# EdgePowerMeter_EasyEDA.net
KiCad netlist of a schematic drawn in EasyEDA
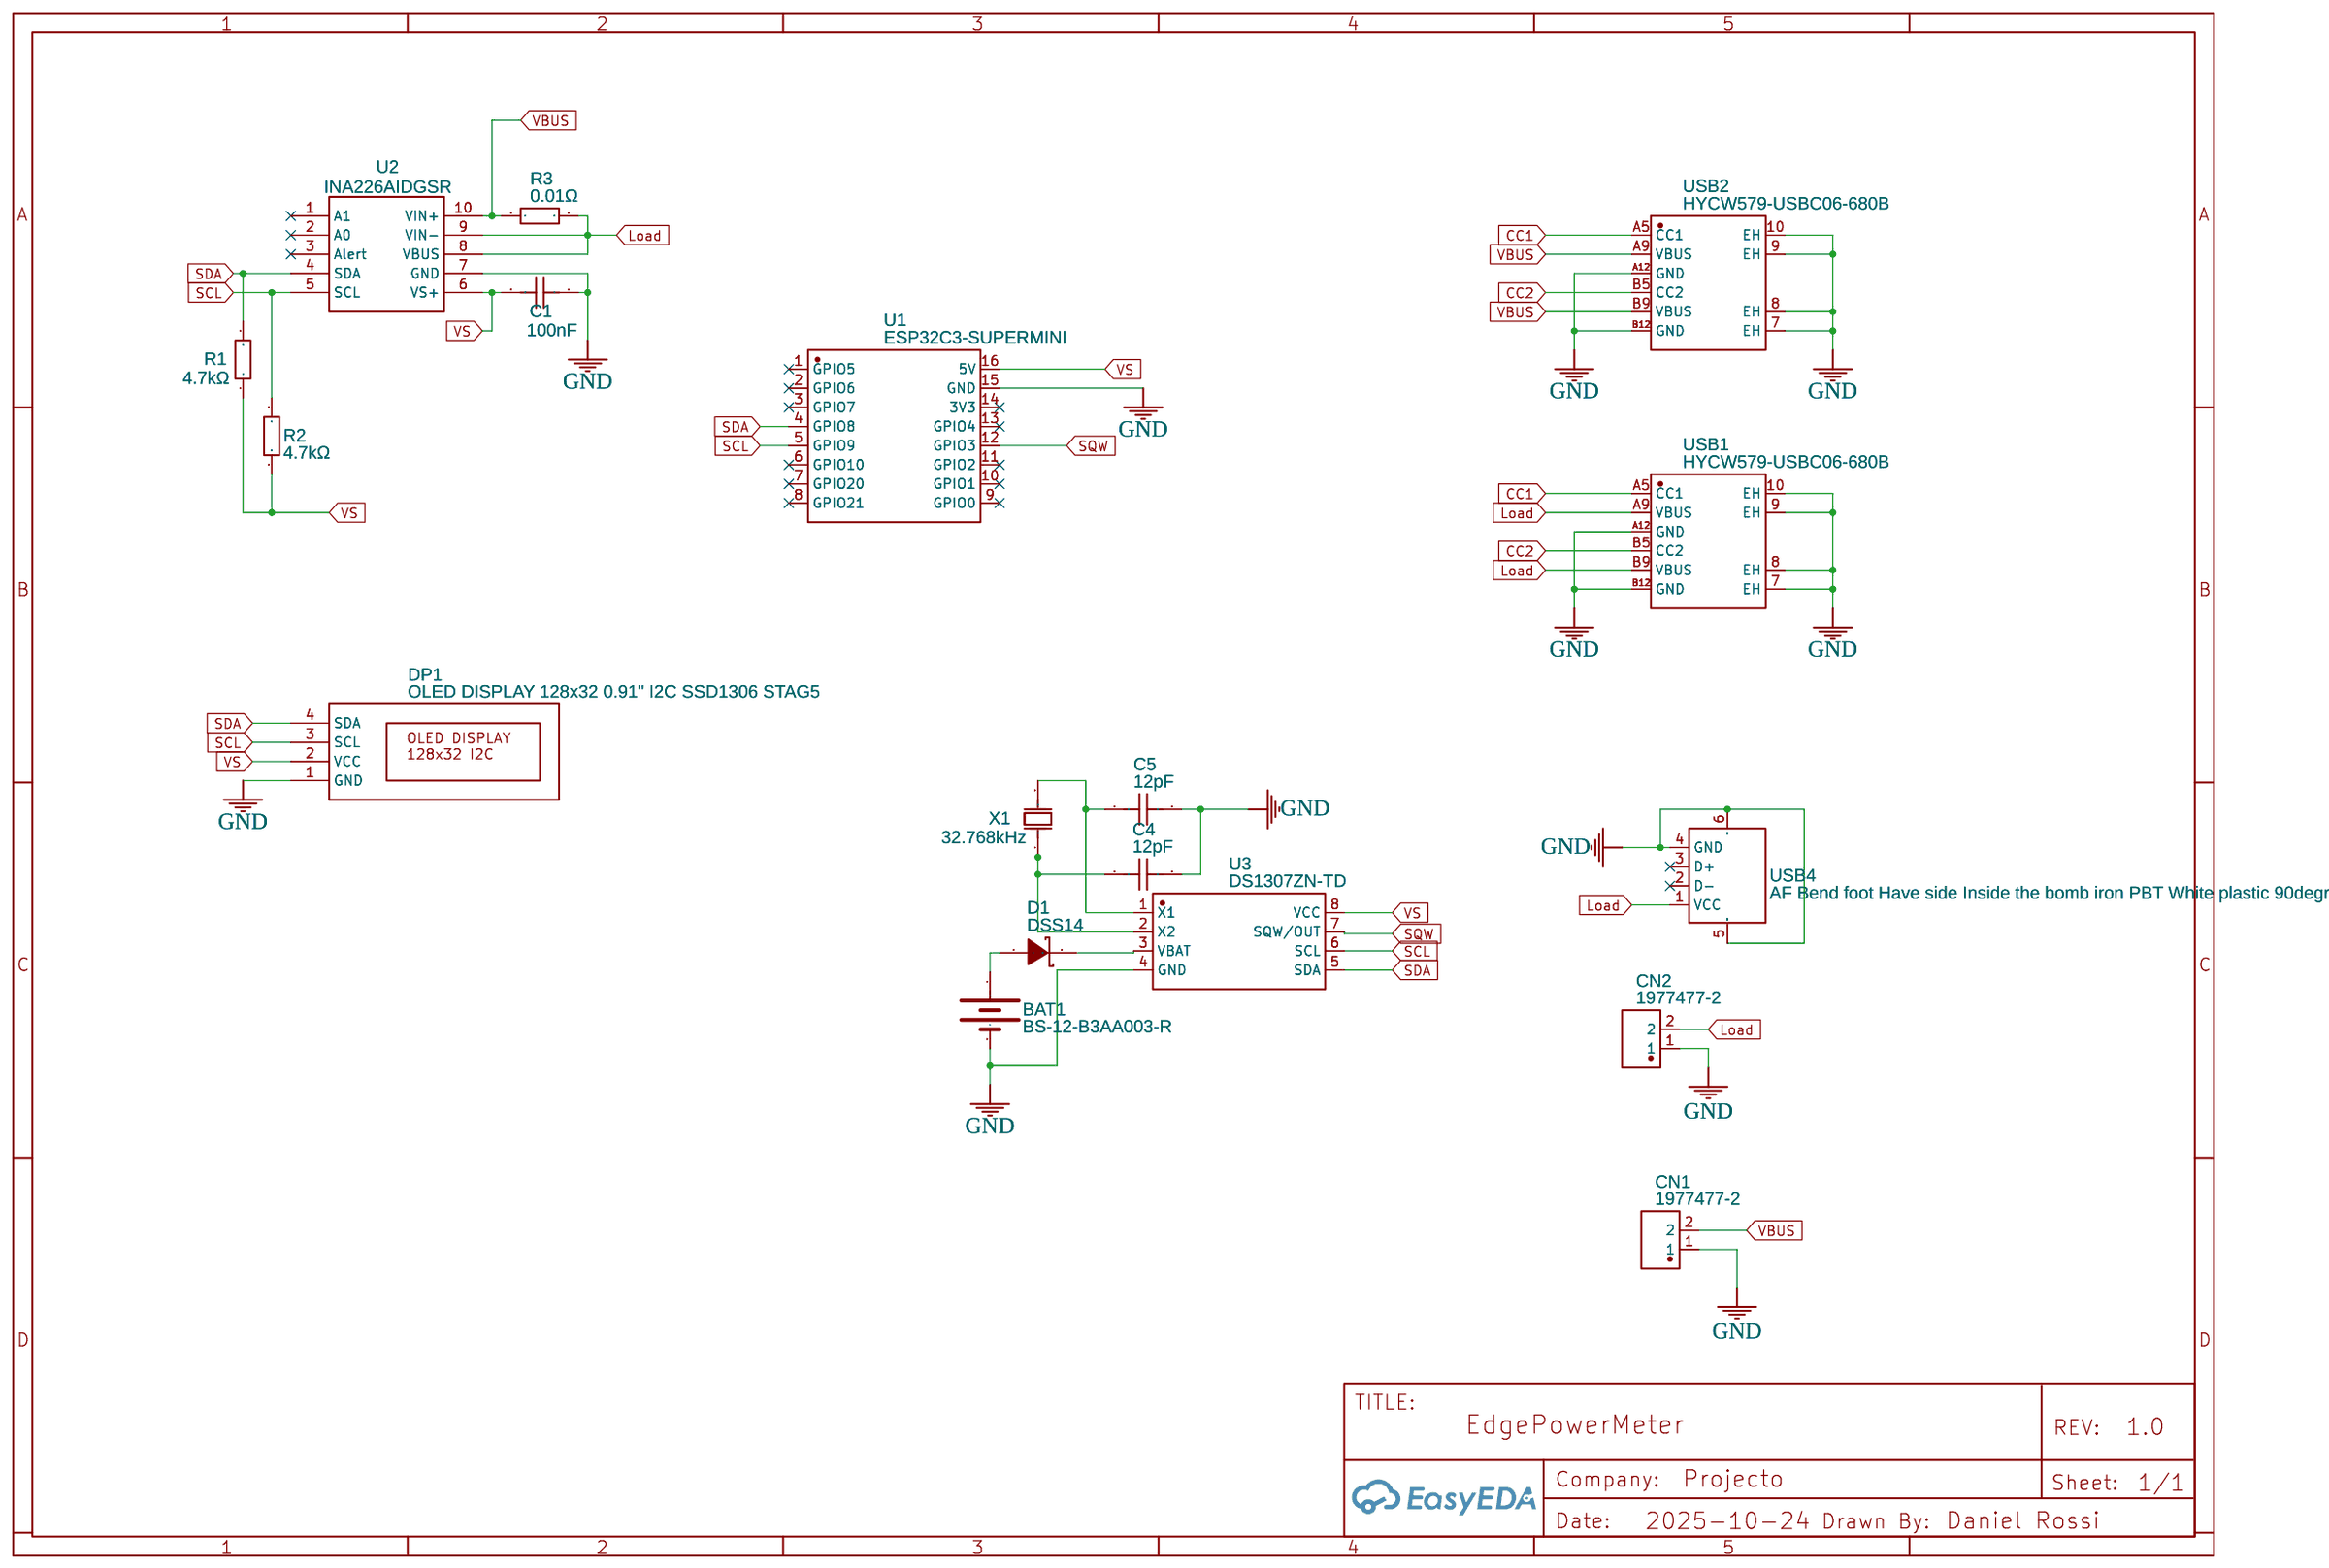
[diagram p0: schematic sheet]

(export (version "E")
  (design (tool "Eeschema 10.0.6"))
  (components
    (comp (ref "BAT1")
      (value "BS-12-B3AA003-R")
      (fields (field (name "Manufacturer") "MYOUNG(美阳)"))
      (libsource (lib "") (part "BS-12-B3AA003-R"))
    )
    (comp (ref "C1")
      (value "100nF")
      (fields
        (field (name "Manufacturer Part") "C1206F104K1RAC3083")
        (field (name "Manufacturer") "KEMET(基美)")
      )
      (libsource (lib "") (part "C1206F104K1RAC3083"))
    )
    (comp (ref "C4") (value "12pF") (libsource (lib "") (part "12PF_1")))
    (comp (ref "C5") (value "12pF") (libsource (lib "") (part "12PF")))
    (comp (ref "CN1")
      (value "1977477-2")
      (fields (field (name "Manufacturer") "TE Connectivity(泰科电子)"))
      (libsource (lib "") (part "1977477-2"))
    )
    (comp (ref "CN2")
      (value "1977477-2")
      (fields (field (name "Manufacturer") "TE Connectivity(泰科电子)"))
      (libsource (lib "") (part "1977477-2"))
    )
    (comp (ref "D1")
      (value "DSS14")
      (fields (field (name "Manufacturer") "星海"))
      (libsource (lib "") (part "DSS14"))
    )
    (comp (ref "DP1")
      (value "OLED DISPLAY 128x32 0.91\" I2C SSD1306 STAG5")
      (libsource (lib "") (part "OLED DISPLAY 128x32 0.91{dblquote} I2C SSD1306 STAG5"))
    )
    (comp (ref "R1")
      (value "4.7kΩ")
      (fields (field (name "Manufacturer Part") "RMC12064.7K1%N") (field (name "Manufacturer") "Tyohm(幸亚电阻)"))
      (libsource (lib "") (part "RMC12064.7K1%N"))
    )
    (comp (ref "R2")
      (value "4.7kΩ")
      (fields (field (name "Manufacturer Part") "RMC12064.7K1%N") (field (name "Manufacturer") "Tyohm(幸亚电阻)"))
      (libsource (lib "") (part "RMC12064.7K1%N"))
    )
    (comp (ref "R3")
      (value "0.01Ω")
      (fields (field (name "Manufacturer Part") "MRF6432(2512)LR010JTS") (field (name "Manufacturer") "SUP"))
      (libsource (lib "") (part "MRF6432(2512)LR010JTS"))
    )
    (comp (ref "U1")
      (value "ESP32C3-SUPERMINI")
      (fields (field (name "Manufacturer Part") "ESP32C3-SuperMini"))
      (libsource (lib "") (part "ESP32C3-SUPERMINI"))
    )
    (comp (ref "U2")
      (value "INA226AIDGSR")
      (fields (field (name "Manufacturer") "TI(德州仪器)"))
      (libsource (lib "") (part "INA226AIDGSR"))
    )
    (comp (ref "U3")
      (value "DS1307ZN-TD")
      (fields (field (name "Manufacturer") "TDSEMIC(拓电半导体)"))
      (libsource (lib "") (part "DS1307ZN-TD"))
    )
    (comp (ref "USB1")
      (value "HYCW579-USBC06-680B")
      (fields (field (name "Manufacturer") "华宇创"))
      (libsource (lib "") (part "HYCW579-USBC06-680B"))
    )
    (comp (ref "USB2")
      (value "HYCW579-USBC06-680B")
      (fields (field (name "Manufacturer") "华宇创"))
      (libsource (lib "") (part "HYCW579-USBC06-680B"))
    )
    (comp (ref "USB4")
      (value "AF Bend foot Have side Inside the bomb iron PBT White plastic 90degree")
      (fields (field (name "Manufacturer Part") "901-131A1011D10100") (field (name "Manufacturer") "精拓金"))
      (libsource (lib "") (part "AF Bend foot Have side Inside the bomb iron PBT White plastic 90degree"))
    )
    (comp (ref "X1")
      (value "32.768kHz")
      (fields
        (field (name "Manufacturer Part") "ABS07-120-32.768KHZ-T")
        (field (name "Manufacturer") "ABRACON")
      )
      (libsource (lib "") (part "ABS07-120-32.768KHZ-T"))
    )
  )
  (nets
    (net (code "1") (name "CC1") (class "Default")
      (node (ref "USB1") (pin "A5") (pinfunction "CC1_A5") (pintype "unspecified"))
      (node (ref "USB2") (pin "A5") (pinfunction "CC1_A5") (pintype "unspecified"))
    )
    (net (code "2") (name "CC2") (class "Default")
      (node (ref "USB1") (pin "B5") (pinfunction "CC2_B5") (pintype "unspecified"))
      (node (ref "USB2") (pin "B5") (pinfunction "CC2_B5") (pintype "unspecified"))
    )
    (net (code "3") (name "GND") (class "Default")
      (node (ref "BAT1") (pin "2") (pinfunction "-_2") (pintype "passive"))
      (node (ref "C1") (pin "1") (pinfunction "1_1") (pintype "unspecified"))
      (node (ref "C4") (pin "1") (pinfunction "1_1") (pintype "unspecified"))
      (node (ref "C5") (pin "2") (pinfunction "2_2") (pintype "unspecified"))
      (node (ref "CN1") (pin "1") (pinfunction "1_1") (pintype "unspecified"))
      (node (ref "CN2") (pin "1") (pinfunction "1_1") (pintype "unspecified"))
      (node (ref "DP1") (pin "1") (pinfunction "GND_1") (pintype "passive"))
      (node (ref "U1") (pin "15") (pinfunction "GND_15") (pintype "unspecified"))
      (node (ref "U2") (pin "7") (pinfunction "GND_7") (pintype "unspecified"))
      (node (ref "U3") (pin "4") (pinfunction "GND_4") (pintype "unspecified"))
      (node (ref "USB1") (pin "10") (pinfunction "EH_10") (pintype "unspecified"))
      (node (ref "USB1") (pin "7") (pinfunction "EH_7") (pintype "unspecified"))
      (node (ref "USB1") (pin "8") (pinfunction "EH_8") (pintype "unspecified"))
      (node (ref "USB1") (pin "9") (pinfunction "EH_9") (pintype "unspecified"))
      (node (ref "USB1") (pin "A12") (pinfunction "GND_A12") (pintype "unspecified"))
      (node (ref "USB1") (pin "B12") (pinfunction "GND_B12") (pintype "unspecified"))
      (node (ref "USB2") (pin "10") (pinfunction "EH_10") (pintype "unspecified"))
      (node (ref "USB2") (pin "7") (pinfunction "EH_7") (pintype "unspecified"))
      (node (ref "USB2") (pin "8") (pinfunction "EH_8") (pintype "unspecified"))
      (node (ref "USB2") (pin "9") (pinfunction "EH_9") (pintype "unspecified"))
      (node (ref "USB2") (pin "A12") (pinfunction "GND_A12") (pintype "unspecified"))
      (node (ref "USB2") (pin "B12") (pinfunction "GND_B12") (pintype "unspecified"))
      (node (ref "USB4") (pin "4") (pinfunction "GND_4") (pintype "input"))
      (node (ref "USB4") (pin "5") (pinfunction "SH2_5") (pintype "unspecified"))
      (node (ref "USB4") (pin "6") (pinfunction "SH1_6") (pintype "unspecified"))
    )
    (net (code "4") (name "Load") (class "Default")
      (node (ref "CN2") (pin "2") (pinfunction "2_2") (pintype "unspecified"))
      (node (ref "R3") (pin "2") (pinfunction "2_2") (pintype "input"))
      (node (ref "U2") (pin "8") (pinfunction "VBUS_8") (pintype "unspecified"))
      (node (ref "U2") (pin "9") (pinfunction "VIN-_9") (pintype "unspecified"))
      (node (ref "USB1") (pin "A9") (pinfunction "VBUS_A9") (pintype "unspecified"))
      (node (ref "USB1") (pin "B9") (pinfunction "VBUS_B9") (pintype "unspecified"))
      (node (ref "USB4") (pin "1") (pinfunction "VCC_1") (pintype "input"))
    )
    (net (code "5") (name "Net-(BAT1-+)") (class "Default")
      (node (ref "BAT1") (pin "1") (pinfunction "+_1") (pintype "passive"))
      (node (ref "D1") (pin "2") (pinfunction "A_2") (pintype "unspecified"))
    )
    (net (code "6") (name "Net-(D1-K)") (class "Default")
      (node (ref "D1") (pin "1") (pinfunction "K_1") (pintype "unspecified"))
      (node (ref "U3") (pin "3") (pinfunction "VBAT_3") (pintype "unspecified"))
    )
    (net (code "7") (name "Net-(U3-X1)") (class "Default")
      (node (ref "C5") (pin "1") (pinfunction "1_1") (pintype "unspecified"))
      (node (ref "U3") (pin "1") (pinfunction "X1_1") (pintype "unspecified"))
      (node (ref "X1") (pin "2") (pinfunction "OSC2_2") (pintype "input"))
    )
    (net (code "8") (name "Net-(U3-X2)") (class "Default")
      (node (ref "C4") (pin "2") (pinfunction "2_2") (pintype "unspecified"))
      (node (ref "U3") (pin "2") (pinfunction "X2_2") (pintype "unspecified"))
      (node (ref "X1") (pin "1") (pinfunction "OSC1_1") (pintype "input"))
    )
    (net (code "9") (name "SCL") (class "Default")
      (node (ref "DP1") (pin "3") (pinfunction "SCL_3") (pintype "input"))
      (node (ref "R2") (pin "2") (pinfunction "2_2") (pintype "unspecified"))
      (node (ref "U1") (pin "5") (pinfunction "GPIO9_5") (pintype "unspecified"))
      (node (ref "U2") (pin "5") (pinfunction "SCL_5") (pintype "unspecified"))
      (node (ref "U3") (pin "6") (pinfunction "SCL_6") (pintype "unspecified"))
    )
    (net (code "10") (name "SDA") (class "Default")
      (node (ref "DP1") (pin "4") (pinfunction "SDA_4") (pintype "input"))
      (node (ref "R1") (pin "2") (pinfunction "2_2") (pintype "unspecified"))
      (node (ref "U1") (pin "4") (pinfunction "GPIO8_4") (pintype "unspecified"))
      (node (ref "U2") (pin "4") (pinfunction "SDA_4") (pintype "unspecified"))
      (node (ref "U3") (pin "5") (pinfunction "SDA_5") (pintype "unspecified"))
    )
    (net (code "11") (name "SQW") (class "Default")
      (node (ref "U1") (pin "12") (pinfunction "GPIO3_12") (pintype "unspecified"))
      (node (ref "U3") (pin "7") (pinfunction "SQW/OUT_7") (pintype "unspecified"))
    )
    (net (code "12") (name "VBUS") (class "Default")
      (node (ref "CN1") (pin "2") (pinfunction "2_2") (pintype "unspecified"))
      (node (ref "R3") (pin "1") (pinfunction "1_1") (pintype "input"))
      (node (ref "U2") (pin "10") (pinfunction "VIN+_10") (pintype "unspecified"))
      (node (ref "USB2") (pin "A9") (pinfunction "VBUS_A9") (pintype "unspecified"))
      (node (ref "USB2") (pin "B9") (pinfunction "VBUS_B9") (pintype "unspecified"))
    )
    (net (code "13") (name "VS") (class "Default")
      (node (ref "C1") (pin "2") (pinfunction "2_2") (pintype "unspecified"))
      (node (ref "DP1") (pin "2") (pinfunction "VCC_2") (pintype "passive"))
      (node (ref "R1") (pin "1") (pinfunction "1_1") (pintype "unspecified"))
      (node (ref "R2") (pin "1") (pinfunction "1_1") (pintype "unspecified"))
      (node (ref "U1") (pin "16") (pinfunction "5V_16") (pintype "unspecified"))
      (node (ref "U2") (pin "6") (pinfunction "VS+_6") (pintype "unspecified"))
      (node (ref "U3") (pin "8") (pinfunction "VCC_8") (pintype "unspecified"))
    )
    (net (code "14") (name "unconnected-(U1-3V3-Pad14)") (class "Default")
      (node (ref "U1") (pin "14") (pinfunction "3V3_14") (pintype "unspecified+no_connect"))
    )
    (net (code "15") (name "unconnected-(U1-GPIO0-Pad9)") (class "Default")
      (node (ref "U1") (pin "9") (pinfunction "GPIO0_9") (pintype "unspecified+no_connect"))
    )
    (net (code "16") (name "unconnected-(U1-GPIO1-Pad10)") (class "Default")
      (node (ref "U1") (pin "10") (pinfunction "GPIO1_10") (pintype "unspecified+no_connect"))
    )
    (net (code "17") (name "unconnected-(U1-GPIO2-Pad11)") (class "Default")
      (node (ref "U1") (pin "11") (pinfunction "GPIO2_11") (pintype "unspecified+no_connect"))
    )
    (net (code "18") (name "unconnected-(U1-GPIO4-Pad13)") (class "Default")
      (node (ref "U1") (pin "13") (pinfunction "GPIO4_13") (pintype "unspecified+no_connect"))
    )
    (net (code "19") (name "unconnected-(U1-GPIO5-Pad1)") (class "Default")
      (node (ref "U1") (pin "1") (pinfunction "GPIO5_1") (pintype "unspecified+no_connect"))
    )
    (net (code "20") (name "unconnected-(U1-GPIO6-Pad2)") (class "Default")
      (node (ref "U1") (pin "2") (pinfunction "GPIO6_2") (pintype "unspecified+no_connect"))
    )
    (net (code "21") (name "unconnected-(U1-GPIO7-Pad3)") (class "Default")
      (node (ref "U1") (pin "3") (pinfunction "GPIO7_3") (pintype "unspecified+no_connect"))
    )
    (net (code "22") (name "unconnected-(U1-GPIO10-Pad6)") (class "Default")
      (node (ref "U1") (pin "6") (pinfunction "GPIO10_6") (pintype "unspecified+no_connect"))
    )
    (net (code "23") (name "unconnected-(U1-GPIO20-Pad7)") (class "Default")
      (node (ref "U1") (pin "7") (pinfunction "GPIO20_7") (pintype "unspecified+no_connect"))
    )
    (net (code "24") (name "unconnected-(U1-GPIO21-Pad8)") (class "Default")
      (node (ref "U1") (pin "8") (pinfunction "GPIO21_8") (pintype "unspecified+no_connect"))
    )
    (net (code "25") (name "unconnected-(U2-A0-Pad2)") (class "Default")
      (node (ref "U2") (pin "2") (pinfunction "A0_2") (pintype "unspecified+no_connect"))
    )
    (net (code "26") (name "unconnected-(U2-A1-Pad1)") (class "Default")
      (node (ref "U2") (pin "1") (pinfunction "A1_1") (pintype "unspecified+no_connect"))
    )
    (net (code "27") (name "unconnected-(U2-Alert-Pad3)") (class "Default")
      (node (ref "U2") (pin "3") (pinfunction "Alert_3") (pintype "unspecified+no_connect"))
    )
    (net (code "28") (name "unconnected-(USB4-D+-Pad3)") (class "Default")
      (node (ref "USB4") (pin "3") (pinfunction "D+_3") (pintype "input+no_connect"))
    )
    (net (code "29") (name "unconnected-(USB4-D--Pad2)") (class "Default")
      (node (ref "USB4") (pin "2") (pinfunction "D-_2") (pintype "input+no_connect"))
    )
  )
)
